# MCU_STM32_SCHE.net
KiCad netlist of a schematic drawn in Altium Designer
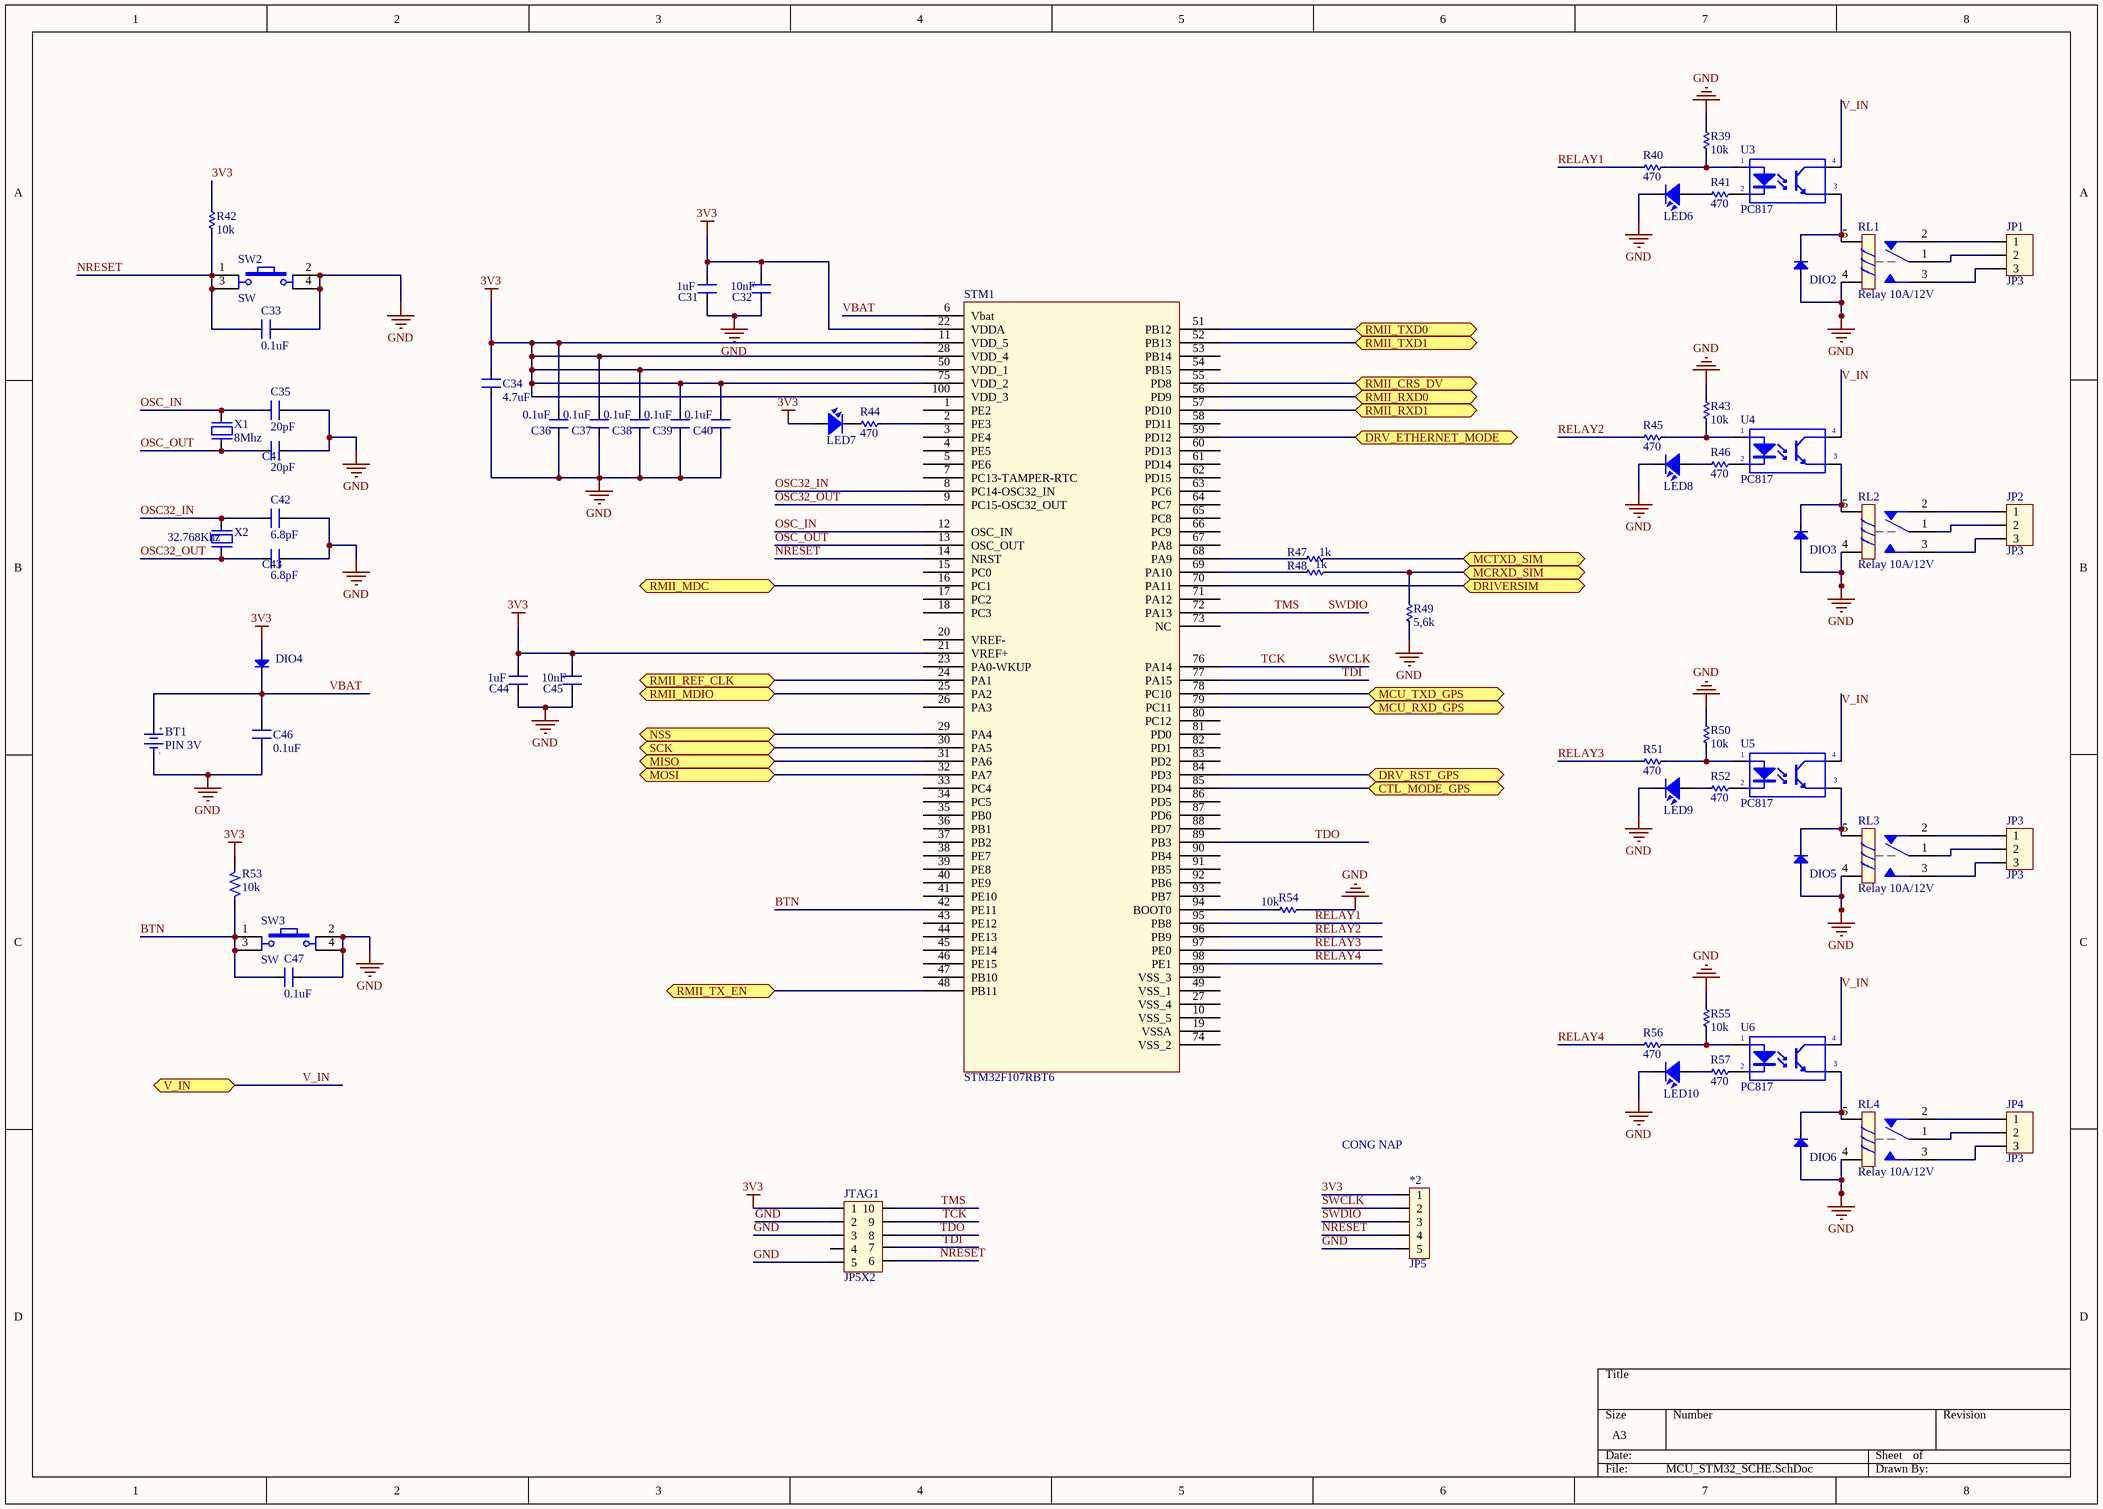
[diagram p0: MCU_STM32_SCHE.SchDoc]

(export (version "E")
  (design (tool "Eeschema 10.0.6"))
  (components
    (comp (ref "*2") (value "JP5") (footprint "JP5") (libsource (lib "syhaunguyen") (part "JP5")))
    (comp (ref "BT1")
      (value "PIN 3V")
      (footprint "PIN3V")
      (description "Battery 3VDC")
      (libsource (lib "syhaunguyen") (part "PIN 3V"))
    )
    (comp (ref "C31")
      (value "1uF")
      (footprint "res 0805 - duplicate")
      (description "Cap SMD")
      (libsource (lib "PART") (part "CM"))
    )
    (comp (ref "C32")
      (value "10nF")
      (footprint "res 0805 - duplicate")
      (description "Cap SMD")
      (libsource (lib "PART") (part "CM"))
    )
    (comp (ref "C33")
      (value "0.1uF")
      (footprint "res 0805 - duplicate")
      (description "Cap SMD")
      (libsource (lib "PART") (part "CM"))
    )
    (comp (ref "C34")
      (value "4.7uF")
      (footprint "res 0805 - duplicate")
      (fields (field (name "DESIGNED BY") "VanDungEvn"))
      (libsource (lib "syhaunguyen") (part "CN"))
    )
    (comp (ref "C35")
      (value "20pF")
      (footprint "res 0805 - duplicate")
      (description "Cap SMD")
      (libsource (lib "PART") (part "CM"))
    )
    (comp (ref "C36")
      (value "0.1uF")
      (footprint "res 0805 - duplicate")
      (description "Cap SMD")
      (libsource (lib "PART") (part "CM"))
    )
    (comp (ref "C37")
      (value "0.1uF")
      (footprint "res 0805 - duplicate")
      (description "Cap SMD")
      (libsource (lib "PART") (part "CM"))
    )
    (comp (ref "C38")
      (value "0.1uF")
      (footprint "res 0805 - duplicate")
      (description "Cap SMD")
      (libsource (lib "PART") (part "CM"))
    )
    (comp (ref "C39")
      (value "0.1uF")
      (footprint "res 0805 - duplicate")
      (description "Cap SMD")
      (libsource (lib "PART") (part "CM"))
    )
    (comp (ref "C40")
      (value "0.1uF")
      (footprint "res 0805 - duplicate")
      (description "Cap SMD")
      (libsource (lib "PART") (part "CM"))
    )
    (comp (ref "C41")
      (value "20pF")
      (footprint "res 0805 - duplicate")
      (description "Cap SMD")
      (libsource (lib "PART") (part "CM"))
    )
    (comp (ref "C42")
      (value "6.8pF")
      (footprint "res 0805 - duplicate")
      (description "Cap SMD")
      (libsource (lib "PART") (part "CM"))
    )
    (comp (ref "C43")
      (value "6.8pF")
      (footprint "res 0805 - duplicate")
      (description "Cap SMD")
      (libsource (lib "PART") (part "CM"))
    )
    (comp (ref "C44")
      (value "1uF")
      (footprint "res 0805 - duplicate")
      (description "Cap SMD")
      (libsource (lib "PART") (part "CM"))
    )
    (comp (ref "C45")
      (value "10nF")
      (footprint "res 0805 - duplicate")
      (description "Cap SMD")
      (libsource (lib "PART") (part "CM"))
    )
    (comp (ref "C46")
      (value "0.1uF")
      (footprint "res 0805 - duplicate")
      (description "Cap SMD")
      (libsource (lib "PART") (part "CM"))
    )
    (comp (ref "C47")
      (value "0.1uF")
      (footprint "res 0805 - duplicate")
      (description "Cap SMD")
      (libsource (lib "PART") (part "CM"))
    )
    (comp (ref "DIO2")
      (value "Diode SMD")
      (footprint "DIOT-SS24")
      (description "Default Diode")
      (fields (field (name "PUBLISHER") "Altium Limited"))
      (libsource (lib "LIBRARYabc") (part "Diode SMD"))
    )
    (comp (ref "DIO3")
      (value "Diode SMD")
      (footprint "DIOT-SS24")
      (description "Default Diode")
      (fields (field (name "PUBLISHER") "Altium Limited"))
      (libsource (lib "LIBRARYabc") (part "Diode SMD"))
    )
    (comp (ref "DIO4")
      (value "Diode SMD")
      (footprint "DIO-SMD-123")
      (description "Default Diode")
      (fields (field (name "PUBLISHER") "Altium Limited"))
      (libsource (lib "LIBRARYabc") (part "Diode SMD"))
    )
    (comp (ref "DIO5")
      (value "Diode SMD")
      (footprint "DIOT-SS24")
      (description "Default Diode")
      (fields (field (name "PUBLISHER") "Altium Limited"))
      (libsource (lib "LIBRARYabc") (part "Diode SMD"))
    )
    (comp (ref "DIO6")
      (value "Diode SMD")
      (footprint "DIOT-SS24")
      (description "Default Diode")
      (fields (field (name "PUBLISHER") "Altium Limited"))
      (libsource (lib "LIBRARYabc") (part "Diode SMD"))
    )
    (comp (ref "JP1")
      (value "JP3")
      (footprint "CON3")
      (description "Connector 3")
      (libsource (lib "syhaunguyen") (part "Con3"))
    )
    (comp (ref "JP2")
      (value "JP3")
      (footprint "CON3")
      (description "Connector 3")
      (libsource (lib "syhaunguyen") (part "Con3"))
    )
    (comp (ref "JP3")
      (value "JP3")
      (footprint "CON3")
      (description "Connector 3")
      (libsource (lib "syhaunguyen") (part "Con3"))
    )
    (comp (ref "JP4")
      (value "JP3")
      (footprint "CON3")
      (description "Connector 3")
      (libsource (lib "syhaunguyen") (part "Con3"))
    )
    (comp (ref "JTAG1") (value "JP5X2") (footprint "JP5X2") (libsource (lib "syhaunguyen") (part "JP5X2")))
    (comp (ref "LED6")
      (value "LED")
      (footprint "res 0805 - duplicate")
      (libsource (lib "LIBRARYabc") (part "LED SMD"))
    )
    (comp (ref "LED7")
      (value "LED")
      (footprint "res 0805 - duplicate")
      (libsource (lib "LIBRARYabc") (part "LED SMD"))
    )
    (comp (ref "LED8")
      (value "LED")
      (footprint "res 0805 - duplicate")
      (libsource (lib "LIBRARYabc") (part "LED SMD"))
    )
    (comp (ref "LED9")
      (value "LED")
      (footprint "res 0805 - duplicate")
      (libsource (lib "LIBRARYabc") (part "LED SMD"))
    )
    (comp (ref "LED10")
      (value "LED")
      (footprint "res 0805 - duplicate")
      (libsource (lib "LIBRARYabc") (part "LED SMD"))
    )
    (comp (ref "R39")
      (value "10k")
      (footprint "res 0805 - duplicate")
      (description "Resistor")
      (fields
        (field (name "MANUFACTURER") "Generic Components")
        (field (name "PUBLISHER") "Altium Hobart Technology Centre")
      )
      (libsource (lib "LIBRARYabc") (part "Res-SMD"))
    )
    (comp (ref "R40")
      (value "470")
      (footprint "res 0805 - duplicate")
      (description "Resistor")
      (fields
        (field (name "MANUFACTURER") "Generic Components")
        (field (name "PUBLISHER") "Altium Hobart Technology Centre")
      )
      (libsource (lib "LIBRARYabc") (part "Res-SMD"))
    )
    (comp (ref "R41")
      (value "470")
      (footprint "res 0805 - duplicate")
      (description "Resistor")
      (fields
        (field (name "MANUFACTURER") "Generic Components")
        (field (name "PUBLISHER") "Altium Hobart Technology Centre")
      )
      (libsource (lib "LIBRARYabc") (part "Res-SMD"))
    )
    (comp (ref "R42")
      (value "10k")
      (footprint "res 0805 - duplicate")
      (description "Resistor")
      (fields
        (field (name "MANUFACTURER") "Generic Components")
        (field (name "PUBLISHER") "Altium Hobart Technology Centre")
      )
      (libsource (lib "LIBRARYabc") (part "Res-SMD"))
    )
    (comp (ref "R43")
      (value "10k")
      (footprint "res 0805 - duplicate")
      (description "Resistor")
      (fields
        (field (name "MANUFACTURER") "Generic Components")
        (field (name "PUBLISHER") "Altium Hobart Technology Centre")
      )
      (libsource (lib "LIBRARYabc") (part "Res-SMD"))
    )
    (comp (ref "R44")
      (value "470")
      (footprint "res 0805 - duplicate")
      (description "Resistor")
      (fields
        (field (name "MANUFACTURER") "Generic Components")
        (field (name "PUBLISHER") "Altium Hobart Technology Centre")
      )
      (libsource (lib "LIBRARYabc") (part "Res-SMD"))
    )
    (comp (ref "R45")
      (value "470")
      (footprint "res 0805 - duplicate")
      (description "Resistor")
      (fields
        (field (name "MANUFACTURER") "Generic Components")
        (field (name "PUBLISHER") "Altium Hobart Technology Centre")
      )
      (libsource (lib "LIBRARYabc") (part "Res-SMD"))
    )
    (comp (ref "R46")
      (value "470")
      (footprint "res 0805 - duplicate")
      (description "Resistor")
      (fields
        (field (name "MANUFACTURER") "Generic Components")
        (field (name "PUBLISHER") "Altium Hobart Technology Centre")
      )
      (libsource (lib "LIBRARYabc") (part "Res-SMD"))
    )
    (comp (ref "R47")
      (value "1k")
      (footprint "res 0805 - duplicate")
      (description "Resistor")
      (fields
        (field (name "MANUFACTURER") "Generic Components")
        (field (name "PUBLISHER") "Altium Hobart Technology Centre")
      )
      (libsource (lib "LIBRARYabc") (part "Res-SMD"))
    )
    (comp (ref "R48")
      (value "1k")
      (footprint "res 0805 - duplicate")
      (description "Resistor")
      (fields
        (field (name "MANUFACTURER") "Generic Components")
        (field (name "PUBLISHER") "Altium Hobart Technology Centre")
      )
      (libsource (lib "LIBRARYabc") (part "Res-SMD"))
    )
    (comp (ref "R49")
      (value "5,6k")
      (footprint "res 0805 - duplicate")
      (description "Resistor")
      (fields
        (field (name "MANUFACTURER") "Generic Components")
        (field (name "PUBLISHER") "Altium Hobart Technology Centre")
      )
      (libsource (lib "LIBRARYabc") (part "Res-SMD"))
    )
    (comp (ref "R50")
      (value "10k")
      (footprint "res 0805 - duplicate")
      (description "Resistor")
      (fields
        (field (name "MANUFACTURER") "Generic Components")
        (field (name "PUBLISHER") "Altium Hobart Technology Centre")
      )
      (libsource (lib "LIBRARYabc") (part "Res-SMD"))
    )
    (comp (ref "R51")
      (value "470")
      (footprint "res 0805 - duplicate")
      (description "Resistor")
      (fields
        (field (name "MANUFACTURER") "Generic Components")
        (field (name "PUBLISHER") "Altium Hobart Technology Centre")
      )
      (libsource (lib "LIBRARYabc") (part "Res-SMD"))
    )
    (comp (ref "R52")
      (value "470")
      (footprint "res 0805 - duplicate")
      (description "Resistor")
      (fields
        (field (name "MANUFACTURER") "Generic Components")
        (field (name "PUBLISHER") "Altium Hobart Technology Centre")
      )
      (libsource (lib "LIBRARYabc") (part "Res-SMD"))
    )
    (comp (ref "R53")
      (value "10k")
      (footprint "res 0805 - duplicate")
      (description "Resistor 1/4W")
      (libsource (lib "syhaunguyen") (part "R"))
    )
    (comp (ref "R54")
      (value "10k")
      (footprint "res 0805 - duplicate")
      (description "Resistor")
      (fields
        (field (name "MANUFACTURER") "Generic Components")
        (field (name "PUBLISHER") "Altium Hobart Technology Centre")
      )
      (libsource (lib "LIBRARYabc") (part "Res-SMD"))
    )
    (comp (ref "R55")
      (value "10k")
      (footprint "res 0805 - duplicate")
      (description "Resistor")
      (fields
        (field (name "MANUFACTURER") "Generic Components")
        (field (name "PUBLISHER") "Altium Hobart Technology Centre")
      )
      (libsource (lib "LIBRARYabc") (part "Res-SMD"))
    )
    (comp (ref "R56")
      (value "470")
      (footprint "res 0805 - duplicate")
      (description "Resistor")
      (fields
        (field (name "MANUFACTURER") "Generic Components")
        (field (name "PUBLISHER") "Altium Hobart Technology Centre")
      )
      (libsource (lib "LIBRARYabc") (part "Res-SMD"))
    )
    (comp (ref "R57")
      (value "470")
      (footprint "res 0805 - duplicate")
      (description "Resistor")
      (fields
        (field (name "MANUFACTURER") "Generic Components")
        (field (name "PUBLISHER") "Altium Hobart Technology Centre")
      )
      (libsource (lib "LIBRARYabc") (part "Res-SMD"))
    )
    (comp (ref "RL1")
      (value "Relay 10A/12V")
      (footprint "RL_SPDT_10A")
      (description "Relay SPDT,10A - 12VDC 5 Pin")
      (libsource (lib "syhaunguyen") (part "Relay 1"))
    )
    (comp (ref "RL2")
      (value "Relay 10A/12V")
      (footprint "RL_SPDT_10A")
      (description "Relay SPDT,10A - 12VDC 5 Pin")
      (libsource (lib "syhaunguyen") (part "Relay 1"))
    )
    (comp (ref "RL3")
      (value "Relay 10A/12V")
      (footprint "RL_SPDT_10A")
      (description "Relay SPDT,10A - 12VDC 5 Pin")
      (libsource (lib "syhaunguyen") (part "Relay 1"))
    )
    (comp (ref "RL4")
      (value "Relay 10A/12V")
      (footprint "RL_SPDT_10A")
      (description "Relay SPDT,10A - 12VDC 5 Pin")
      (libsource (lib "syhaunguyen") (part "Relay 1"))
    )
    (comp (ref "STM1")
      (value "STM32F107RBT6")
      (footprint "STM32F107RBT6-LQFP100")
      (libsource (lib "my_lib") (part "STM32F107RBT6"))
    )
    (comp (ref "SW2")
      (value "SW")
      (footprint "button")
      (description "Switch button 4 pin")
      (libsource (lib "syhaunguyen") (part "SW4"))
    )
    (comp (ref "SW3")
      (value "SW")
      (footprint "button")
      (description "Switch button 4 pin")
      (libsource (lib "syhaunguyen") (part "SW4"))
    )
    (comp (ref "U3")
      (value "PC817")
      (footprint "DIP4/W0.3")
      (description "Single Opto")
      (libsource (lib "syhaunguyen") (part "PC817"))
    )
    (comp (ref "U4")
      (value "PC817")
      (footprint "DIP4/W0.3")
      (description "Single Opto")
      (libsource (lib "syhaunguyen") (part "PC817"))
    )
    (comp (ref "U5")
      (value "PC817")
      (footprint "DIP4/W0.3")
      (description "Single Opto")
      (libsource (lib "syhaunguyen") (part "PC817"))
    )
    (comp (ref "U6")
      (value "PC817")
      (footprint "DIP4/W0.3")
      (description "Single Opto")
      (libsource (lib "syhaunguyen") (part "PC817"))
    )
    (comp (ref "X1")
      (value "8Mhz")
      (footprint "XT2")
      (description "Crystal, 32.768 KHz, -40 to 85 degC, 3.2 x 1.5 x 0.9 mm SMD")
      (libsource (lib "LIBRARYabc") (part "XT2"))
    )
    (comp (ref "X2")
      (value "32.768Khz")
      (footprint "XT2")
      (description "Crystal, 32.768 KHz, -40 to 85 degC, 3.2 x 1.5 x 0.9 mm SMD")
      (libsource (lib "LIBRARYabc") (part "XT2"))
    )
  )
  (nets
    (net (code "1") (name "/BTN") (class "Default")
      (node (ref "C47") (pin "1") (pinfunction "1_1") (pintype "passive"))
      (node (ref "R53") (pin "1") (pinfunction "1_1") (pintype "passive"))
      (node (ref "STM1") (pin "42") (pinfunction "PE11_42") (pintype "passive"))
      (node (ref "SW3") (pin "1") (pintype "passive"))
      (node (ref "SW3") (pin "3") (pintype "passive"))
    )
    (net (code "2") (name "/CTL_MODE_GPS") (class "Default")
      (node (ref "STM1") (pin "85") (pinfunction "PD4_85") (pintype "passive"))
    )
    (net (code "3") (name "/DRIVERSIM") (class "Default")
      (node (ref "STM1") (pin "70") (pinfunction "PA11_70") (pintype "passive"))
    )
    (net (code "4") (name "/DRV_ETHERNET_MODE") (class "Default")
      (node (ref "STM1") (pin "59") (pinfunction "PD12_59") (pintype "passive"))
    )
    (net (code "5") (name "/DRV_RST_GPS") (class "Default")
      (node (ref "STM1") (pin "84") (pinfunction "PD3_84") (pintype "passive"))
    )
    (net (code "6") (name "/MCRXD_SIM") (class "Default")
      (node (ref "R48") (pin "1") (pinfunction "1_1") (pintype "passive"))
      (node (ref "R49") (pin "1") (pinfunction "1_1") (pintype "passive"))
    )
    (net (code "7") (name "/MCTXD_SIM") (class "Default")
      (node (ref "R47") (pin "1") (pinfunction "1_1") (pintype "passive"))
    )
    (net (code "8") (name "/MCU_RXD_GPS") (class "Default")
      (node (ref "STM1") (pin "79") (pinfunction "PC11_79") (pintype "passive"))
    )
    (net (code "9") (name "/MCU_TXD_GPS") (class "Default")
      (node (ref "STM1") (pin "78") (pinfunction "PC10_78") (pintype "passive"))
    )
    (net (code "10") (name "/MISO") (class "Default")
      (node (ref "STM1") (pin "31") (pinfunction "PA6_31") (pintype "passive"))
    )
    (net (code "11") (name "/MOSI") (class "Default")
      (node (ref "STM1") (pin "32") (pinfunction "PA7_32") (pintype "passive"))
    )
    (net (code "12") (name "/NRESET") (class "Default")
      (node (ref "*2") (pin "4") (pinfunction "4_4") (pintype "passive"))
      (node (ref "C33") (pin "1") (pinfunction "1_1") (pintype "passive"))
      (node (ref "JTAG1") (pin "6") (pinfunction "6_6") (pintype "passive"))
      (node (ref "R42") (pin "2") (pinfunction "2_2") (pintype "passive"))
      (node (ref "STM1") (pin "14") (pinfunction "NRST_14") (pintype "passive"))
      (node (ref "SW2") (pin "1") (pintype "passive"))
      (node (ref "SW2") (pin "3") (pintype "passive"))
    )
    (net (code "13") (name "/NSS") (class "Default")
      (node (ref "STM1") (pin "29") (pinfunction "PA4_29") (pintype "passive"))
    )
    (net (code "14") (name "/OSC32_IN") (class "Default")
      (node (ref "C42") (pin "1") (pinfunction "1_1") (pintype "passive"))
      (node (ref "STM1") (pin "8") (pinfunction "PC14-OSC32_IN_8") (pintype "passive"))
      (node (ref "X2") (pin "2") (pinfunction "2_2") (pintype "passive"))
    )
    (net (code "15") (name "/OSC32_OUT") (class "Default")
      (node (ref "C43") (pin "1") (pinfunction "1_1") (pintype "passive"))
      (node (ref "STM1") (pin "9") (pinfunction "PC15-OSC32_OUT_9") (pintype "passive"))
      (node (ref "X2") (pin "1") (pinfunction "1_1") (pintype "passive"))
    )
    (net (code "16") (name "/OSC_IN") (class "Default")
      (node (ref "C35") (pin "1") (pinfunction "1_1") (pintype "passive"))
      (node (ref "STM1") (pin "12") (pinfunction "OSC_IN_12") (pintype "passive"))
      (node (ref "X1") (pin "2") (pinfunction "2_2") (pintype "passive"))
    )
    (net (code "17") (name "/OSC_OUT") (class "Default")
      (node (ref "C41") (pin "1") (pinfunction "1_1") (pintype "passive"))
      (node (ref "STM1") (pin "13") (pinfunction "OSC_OUT_13") (pintype "passive"))
      (node (ref "X1") (pin "1") (pinfunction "1_1") (pintype "passive"))
    )
    (net (code "18") (name "/RELAY1") (class "Default")
      (node (ref "R40") (pin "2") (pinfunction "2_2") (pintype "passive"))
      (node (ref "STM1") (pin "95") (pinfunction "PB8_95") (pintype "passive"))
    )
    (net (code "19") (name "/RELAY2") (class "Default")
      (node (ref "R45") (pin "2") (pinfunction "2_2") (pintype "passive"))
      (node (ref "STM1") (pin "96") (pinfunction "PB9_96") (pintype "passive"))
    )
    (net (code "20") (name "/RELAY3") (class "Default")
      (node (ref "R51") (pin "2") (pinfunction "2_2") (pintype "passive"))
      (node (ref "STM1") (pin "97") (pinfunction "PE0_97") (pintype "passive"))
    )
    (net (code "21") (name "/RELAY4") (class "Default")
      (node (ref "R56") (pin "2") (pinfunction "2_2") (pintype "passive"))
      (node (ref "STM1") (pin "98") (pinfunction "PE1_98") (pintype "passive"))
    )
    (net (code "22") (name "/RMII_CRS_DV") (class "Default")
      (node (ref "STM1") (pin "55") (pinfunction "PD8_55") (pintype "passive"))
    )
    (net (code "23") (name "/RMII_MDC") (class "Default")
      (node (ref "STM1") (pin "16") (pinfunction "PC1_16") (pintype "passive"))
    )
    (net (code "24") (name "/RMII_MDIO") (class "Default")
      (node (ref "STM1") (pin "25") (pinfunction "PA2_25") (pintype "passive"))
    )
    (net (code "25") (name "/RMII_REF_CLK") (class "Default")
      (node (ref "STM1") (pin "24") (pinfunction "PA1_24") (pintype "passive"))
    )
    (net (code "26") (name "/RMII_RXD0") (class "Default")
      (node (ref "STM1") (pin "56") (pinfunction "PD9_56") (pintype "passive"))
    )
    (net (code "27") (name "/RMII_RXD1") (class "Default")
      (node (ref "STM1") (pin "57") (pinfunction "PD10_57") (pintype "passive"))
    )
    (net (code "28") (name "/RMII_TXD0") (class "Default")
      (node (ref "STM1") (pin "51") (pinfunction "PB12_51") (pintype "passive"))
    )
    (net (code "29") (name "/RMII_TXD1") (class "Default")
      (node (ref "STM1") (pin "52") (pinfunction "PB13_52") (pintype "passive"))
    )
    (net (code "30") (name "/RMII_TX_EN") (class "Default")
      (node (ref "STM1") (pin "48") (pinfunction "PB11_48") (pintype "passive"))
    )
    (net (code "31") (name "/SCK") (class "Default")
      (node (ref "STM1") (pin "30") (pinfunction "PA5_30") (pintype "passive"))
    )
    (net (code "32") (name "/SWCLK") (class "Default")
      (node (ref "*2") (pin "2") (pinfunction "2_2") (pintype "passive"))
      (node (ref "JTAG1") (pin "9") (pinfunction "9_9") (pintype "passive"))
      (node (ref "STM1") (pin "76") (pinfunction "PA14_76") (pintype "passive"))
    )
    (net (code "33") (name "/SWDIO") (class "Default")
      (node (ref "*2") (pin "3") (pinfunction "3_3") (pintype "passive"))
      (node (ref "JTAG1") (pin "10") (pinfunction "10_10") (pintype "passive"))
      (node (ref "STM1") (pin "72") (pinfunction "PA13_72") (pintype "passive"))
    )
    (net (code "34") (name "/TDI") (class "Default")
      (node (ref "JTAG1") (pin "7") (pinfunction "7_7") (pintype "passive"))
      (node (ref "STM1") (pin "77") (pinfunction "PA15_77") (pintype "passive"))
    )
    (net (code "35") (name "/TDO") (class "Default")
      (node (ref "JTAG1") (pin "8") (pinfunction "8_8") (pintype "passive"))
      (node (ref "STM1") (pin "89") (pinfunction "PB3_89") (pintype "passive"))
    )
    (net (code "36") (name "/VBAT") (class "Default")
      (node (ref "BT1") (pin "1") (pinfunction "+3V_1") (pintype "passive"))
      (node (ref "C46") (pin "2") (pinfunction "2_2") (pintype "passive"))
      (node (ref "DIO4") (pin "2") (pinfunction "K_2") (pintype "passive"))
      (node (ref "STM1") (pin "6") (pinfunction "Vbat_6") (pintype "passive"))
    )
    (net (code "37") (name "/V_IN") (class "Default")
      (node (ref "U3") (pin "4") (pinfunction "C_4") (pintype "passive"))
      (node (ref "U4") (pin "4") (pinfunction "C_4") (pintype "passive"))
      (node (ref "U5") (pin "4") (pinfunction "C_4") (pintype "passive"))
      (node (ref "U6") (pin "4") (pinfunction "C_4") (pintype "passive"))
    )
    (net (code "38") (name "3V3") (class "Default")
      (node (ref "*2") (pin "1") (pinfunction "1_1") (pintype "passive"))
      (node (ref "C31") (pin "2") (pinfunction "2_2") (pintype "passive"))
      (node (ref "C32") (pin "2") (pinfunction "2_2") (pintype "passive"))
      (node (ref "C34") (pin "2") (pinfunction "2_2") (pintype "passive"))
      (node (ref "C36") (pin "2") (pinfunction "2_2") (pintype "passive"))
      (node (ref "C37") (pin "2") (pinfunction "2_2") (pintype "passive"))
      (node (ref "C38") (pin "2") (pinfunction "2_2") (pintype "passive"))
      (node (ref "C39") (pin "2") (pinfunction "2_2") (pintype "passive"))
      (node (ref "C40") (pin "2") (pinfunction "2_2") (pintype "passive"))
      (node (ref "C44") (pin "2") (pinfunction "2_2") (pintype "passive"))
      (node (ref "C45") (pin "2") (pinfunction "2_2") (pintype "passive"))
      (node (ref "DIO4") (pin "1") (pinfunction "A_1") (pintype "passive"))
      (node (ref "JTAG1") (pin "1") (pinfunction "1_1") (pintype "passive"))
      (node (ref "LED7") (pin "1") (pinfunction "1_1") (pintype "passive"))
      (node (ref "R42") (pin "1") (pinfunction "1_1") (pintype "passive"))
      (node (ref "R53") (pin "2") (pinfunction "2_2") (pintype "passive"))
      (node (ref "STM1") (pin "100") (pinfunction "VDD_3_100") (pintype "passive"))
      (node (ref "STM1") (pin "11") (pinfunction "VDD_5_11") (pintype "passive"))
      (node (ref "STM1") (pin "21") (pinfunction "VREF+_21") (pintype "passive"))
      (node (ref "STM1") (pin "22") (pinfunction "VDDA_22") (pintype "passive"))
      (node (ref "STM1") (pin "28") (pinfunction "VDD_4_28") (pintype "passive"))
      (node (ref "STM1") (pin "50") (pinfunction "VDD_1_50") (pintype "passive"))
      (node (ref "STM1") (pin "75") (pinfunction "VDD_2_75") (pintype "passive"))
    )
    (net (code "39") (name "GND") (class "Default")
      (node (ref "*2") (pin "5") (pinfunction "5_5") (pintype "passive"))
      (node (ref "BT1") (pin "2") (pinfunction "GND_2") (pintype "passive"))
      (node (ref "C31") (pin "1") (pinfunction "1_1") (pintype "passive"))
      (node (ref "C32") (pin "1") (pinfunction "1_1") (pintype "passive"))
      (node (ref "C33") (pin "2") (pinfunction "2_2") (pintype "passive"))
      (node (ref "C34") (pin "1") (pinfunction "1_1") (pintype "passive"))
      (node (ref "C35") (pin "2") (pinfunction "2_2") (pintype "passive"))
      (node (ref "C36") (pin "1") (pinfunction "1_1") (pintype "passive"))
      (node (ref "C37") (pin "1") (pinfunction "1_1") (pintype "passive"))
      (node (ref "C38") (pin "1") (pinfunction "1_1") (pintype "passive"))
      (node (ref "C39") (pin "1") (pinfunction "1_1") (pintype "passive"))
      (node (ref "C40") (pin "1") (pinfunction "1_1") (pintype "passive"))
      (node (ref "C41") (pin "2") (pinfunction "2_2") (pintype "passive"))
      (node (ref "C42") (pin "2") (pinfunction "2_2") (pintype "passive"))
      (node (ref "C43") (pin "2") (pinfunction "2_2") (pintype "passive"))
      (node (ref "C44") (pin "1") (pinfunction "1_1") (pintype "passive"))
      (node (ref "C45") (pin "1") (pinfunction "1_1") (pintype "passive"))
      (node (ref "C46") (pin "1") (pinfunction "1_1") (pintype "passive"))
      (node (ref "C47") (pin "2") (pinfunction "2_2") (pintype "passive"))
      (node (ref "DIO2") (pin "1") (pinfunction "A_1") (pintype "passive"))
      (node (ref "DIO3") (pin "1") (pinfunction "A_1") (pintype "passive"))
      (node (ref "DIO5") (pin "1") (pinfunction "A_1") (pintype "passive"))
      (node (ref "DIO6") (pin "1") (pinfunction "A_1") (pintype "passive"))
      (node (ref "JTAG1") (pin "2") (pinfunction "2_2") (pintype "passive"))
      (node (ref "JTAG1") (pin "3") (pinfunction "3_3") (pintype "passive"))
      (node (ref "JTAG1") (pin "5") (pinfunction "5_5") (pintype "passive"))
      (node (ref "LED10") (pin "2") (pinfunction "2_2") (pintype "passive"))
      (node (ref "LED6") (pin "2") (pinfunction "2_2") (pintype "passive"))
      (node (ref "LED8") (pin "2") (pinfunction "2_2") (pintype "passive"))
      (node (ref "LED9") (pin "2") (pinfunction "2_2") (pintype "passive"))
      (node (ref "R39") (pin "1") (pinfunction "1_1") (pintype "passive"))
      (node (ref "R43") (pin "1") (pinfunction "1_1") (pintype "passive"))
      (node (ref "R49") (pin "2") (pinfunction "2_2") (pintype "passive"))
      (node (ref "R50") (pin "1") (pinfunction "1_1") (pintype "passive"))
      (node (ref "R54") (pin "2") (pinfunction "2_2") (pintype "passive"))
      (node (ref "R55") (pin "1") (pinfunction "1_1") (pintype "passive"))
      (node (ref "RL1") (pin "4") (pinfunction "4_4") (pintype "passive"))
      (node (ref "RL2") (pin "4") (pinfunction "4_4") (pintype "passive"))
      (node (ref "RL3") (pin "4") (pinfunction "4_4") (pintype "passive"))
      (node (ref "RL4") (pin "4") (pinfunction "4_4") (pintype "passive"))
      (node (ref "SW2") (pin "2") (pintype "passive"))
      (node (ref "SW2") (pin "4") (pintype "passive"))
      (node (ref "SW3") (pin "2") (pintype "passive"))
      (node (ref "SW3") (pin "4") (pintype "passive"))
    )
    (net (code "40") (name "Net-(DIO2-K)") (class "Default")
      (node (ref "DIO2") (pin "2") (pinfunction "K_2") (pintype "passive"))
      (node (ref "RL1") (pin "5") (pinfunction "5_5") (pintype "passive"))
      (node (ref "U3") (pin "3") (pinfunction "E_3") (pintype "passive"))
    )
    (net (code "41") (name "Net-(DIO3-K)") (class "Default")
      (node (ref "DIO3") (pin "2") (pinfunction "K_2") (pintype "passive"))
      (node (ref "RL2") (pin "5") (pinfunction "5_5") (pintype "passive"))
      (node (ref "U4") (pin "3") (pinfunction "E_3") (pintype "passive"))
    )
    (net (code "42") (name "Net-(DIO5-K)") (class "Default")
      (node (ref "DIO5") (pin "2") (pinfunction "K_2") (pintype "passive"))
      (node (ref "RL3") (pin "5") (pinfunction "5_5") (pintype "passive"))
      (node (ref "U5") (pin "3") (pinfunction "E_3") (pintype "passive"))
    )
    (net (code "43") (name "Net-(DIO6-K)") (class "Default")
      (node (ref "DIO6") (pin "2") (pinfunction "K_2") (pintype "passive"))
      (node (ref "RL4") (pin "5") (pinfunction "5_5") (pintype "passive"))
      (node (ref "U6") (pin "3") (pinfunction "E_3") (pintype "passive"))
    )
    (net (code "44") (name "Net-(JP1-Pad1)") (class "Default")
      (node (ref "JP1") (pin "1") (pinfunction "1_1") (pintype "passive"))
      (node (ref "RL1") (pin "2") (pinfunction "2_2") (pintype "passive"))
    )
    (net (code "45") (name "Net-(JP1-Pad2)") (class "Default")
      (node (ref "JP1") (pin "2") (pinfunction "2_2") (pintype "passive"))
      (node (ref "RL1") (pin "1") (pinfunction "1_1") (pintype "passive"))
    )
    (net (code "46") (name "Net-(JP1-Pad3)") (class "Default")
      (node (ref "JP1") (pin "3") (pinfunction "3_3") (pintype "passive"))
      (node (ref "RL1") (pin "3") (pinfunction "3_3") (pintype "passive"))
    )
    (net (code "47") (name "Net-(JP2-Pad1)") (class "Default")
      (node (ref "JP2") (pin "1") (pinfunction "1_1") (pintype "passive"))
      (node (ref "RL2") (pin "2") (pinfunction "2_2") (pintype "passive"))
    )
    (net (code "48") (name "Net-(JP2-Pad2)") (class "Default")
      (node (ref "JP2") (pin "2") (pinfunction "2_2") (pintype "passive"))
      (node (ref "RL2") (pin "1") (pinfunction "1_1") (pintype "passive"))
    )
    (net (code "49") (name "Net-(JP2-Pad3)") (class "Default")
      (node (ref "JP2") (pin "3") (pinfunction "3_3") (pintype "passive"))
      (node (ref "RL2") (pin "3") (pinfunction "3_3") (pintype "passive"))
    )
    (net (code "50") (name "Net-(JP3-Pad1)") (class "Default")
      (node (ref "JP3") (pin "1") (pinfunction "1_1") (pintype "passive"))
      (node (ref "RL3") (pin "2") (pinfunction "2_2") (pintype "passive"))
    )
    (net (code "51") (name "Net-(JP3-Pad2)") (class "Default")
      (node (ref "JP3") (pin "2") (pinfunction "2_2") (pintype "passive"))
      (node (ref "RL3") (pin "1") (pinfunction "1_1") (pintype "passive"))
    )
    (net (code "52") (name "Net-(JP3-Pad3)") (class "Default")
      (node (ref "JP3") (pin "3") (pinfunction "3_3") (pintype "passive"))
      (node (ref "RL3") (pin "3") (pinfunction "3_3") (pintype "passive"))
    )
    (net (code "53") (name "Net-(JP4-Pad1)") (class "Default")
      (node (ref "JP4") (pin "1") (pinfunction "1_1") (pintype "passive"))
      (node (ref "RL4") (pin "2") (pinfunction "2_2") (pintype "passive"))
    )
    (net (code "54") (name "Net-(JP4-Pad2)") (class "Default")
      (node (ref "JP4") (pin "2") (pinfunction "2_2") (pintype "passive"))
      (node (ref "RL4") (pin "1") (pinfunction "1_1") (pintype "passive"))
    )
    (net (code "55") (name "Net-(JP4-Pad3)") (class "Default")
      (node (ref "JP4") (pin "3") (pinfunction "3_3") (pintype "passive"))
      (node (ref "RL4") (pin "3") (pinfunction "3_3") (pintype "passive"))
    )
    (net (code "56") (name "Net-(LED6-Pad1)") (class "Default")
      (node (ref "LED6") (pin "1") (pinfunction "1_1") (pintype "passive"))
      (node (ref "R41") (pin "2") (pinfunction "2_2") (pintype "passive"))
    )
    (net (code "57") (name "Net-(LED7-Pad2)") (class "Default")
      (node (ref "LED7") (pin "2") (pinfunction "2_2") (pintype "passive"))
      (node (ref "R44") (pin "2") (pinfunction "2_2") (pintype "passive"))
    )
    (net (code "58") (name "Net-(LED8-Pad1)") (class "Default")
      (node (ref "LED8") (pin "1") (pinfunction "1_1") (pintype "passive"))
      (node (ref "R46") (pin "2") (pinfunction "2_2") (pintype "passive"))
    )
    (net (code "59") (name "Net-(LED9-Pad1)") (class "Default")
      (node (ref "LED9") (pin "1") (pinfunction "1_1") (pintype "passive"))
      (node (ref "R52") (pin "2") (pinfunction "2_2") (pintype "passive"))
    )
    (net (code "60") (name "Net-(LED10-Pad1)") (class "Default")
      (node (ref "LED10") (pin "1") (pinfunction "1_1") (pintype "passive"))
      (node (ref "R57") (pin "2") (pinfunction "2_2") (pintype "passive"))
    )
    (net (code "61") (name "Net-(STM1-BOOT0)") (class "Default")
      (node (ref "R54") (pin "1") (pinfunction "1_1") (pintype "passive"))
      (node (ref "STM1") (pin "94") (pinfunction "BOOT0_94") (pintype "passive"))
    )
    (net (code "62") (name "Net-(STM1-PA9)") (class "Default")
      (node (ref "R47") (pin "2") (pinfunction "2_2") (pintype "passive"))
      (node (ref "STM1") (pin "68") (pinfunction "PA9_68") (pintype "passive"))
    )
    (net (code "63") (name "Net-(STM1-PA10)") (class "Default")
      (node (ref "R48") (pin "2") (pinfunction "2_2") (pintype "passive"))
      (node (ref "STM1") (pin "69") (pinfunction "PA10_69") (pintype "passive"))
    )
    (net (code "64") (name "Net-(STM1-PE3)") (class "Default")
      (node (ref "R44") (pin "1") (pinfunction "1_1") (pintype "passive"))
      (node (ref "STM1") (pin "2") (pinfunction "PE3_2") (pintype "passive"))
    )
    (net (code "65") (name "Net-(U3-A)") (class "Default")
      (node (ref "R39") (pin "2") (pinfunction "2_2") (pintype "passive"))
      (node (ref "R40") (pin "1") (pinfunction "1_1") (pintype "passive"))
      (node (ref "U3") (pin "1") (pinfunction "A_1") (pintype "passive"))
    )
    (net (code "66") (name "Net-(U3-K)") (class "Default")
      (node (ref "R41") (pin "1") (pinfunction "1_1") (pintype "passive"))
      (node (ref "U3") (pin "2") (pinfunction "K_2") (pintype "passive"))
    )
    (net (code "67") (name "Net-(U4-A)") (class "Default")
      (node (ref "R43") (pin "2") (pinfunction "2_2") (pintype "passive"))
      (node (ref "R45") (pin "1") (pinfunction "1_1") (pintype "passive"))
      (node (ref "U4") (pin "1") (pinfunction "A_1") (pintype "passive"))
    )
    (net (code "68") (name "Net-(U4-K)") (class "Default")
      (node (ref "R46") (pin "1") (pinfunction "1_1") (pintype "passive"))
      (node (ref "U4") (pin "2") (pinfunction "K_2") (pintype "passive"))
    )
    (net (code "69") (name "Net-(U5-A)") (class "Default")
      (node (ref "R50") (pin "2") (pinfunction "2_2") (pintype "passive"))
      (node (ref "R51") (pin "1") (pinfunction "1_1") (pintype "passive"))
      (node (ref "U5") (pin "1") (pinfunction "A_1") (pintype "passive"))
    )
    (net (code "70") (name "Net-(U5-K)") (class "Default")
      (node (ref "R52") (pin "1") (pinfunction "1_1") (pintype "passive"))
      (node (ref "U5") (pin "2") (pinfunction "K_2") (pintype "passive"))
    )
    (net (code "71") (name "Net-(U6-A)") (class "Default")
      (node (ref "R55") (pin "2") (pinfunction "2_2") (pintype "passive"))
      (node (ref "R56") (pin "1") (pinfunction "1_1") (pintype "passive"))
      (node (ref "U6") (pin "1") (pinfunction "A_1") (pintype "passive"))
    )
    (net (code "72") (name "Net-(U6-K)") (class "Default")
      (node (ref "R57") (pin "1") (pinfunction "1_1") (pintype "passive"))
      (node (ref "U6") (pin "2") (pinfunction "K_2") (pintype "passive"))
    )
    (net (code "73") (name "unconnected-(JTAG1-Pad4)") (class "Default")
      (node (ref "JTAG1") (pin "4") (pinfunction "4_4") (pintype "passive"))
    )
    (net (code "74") (name "unconnected-(STM1-NC-Pad73)") (class "Default")
      (node (ref "STM1") (pin "73") (pinfunction "NC_73") (pintype "passive"))
    )
    (net (code "75") (name "unconnected-(STM1-PA0-WKUP-Pad23)") (class "Default")
      (node (ref "STM1") (pin "23") (pinfunction "PA0-WKUP_23") (pintype "passive"))
    )
    (net (code "76") (name "unconnected-(STM1-PA3-Pad26)") (class "Default")
      (node (ref "STM1") (pin "26") (pinfunction "PA3_26") (pintype "passive"))
    )
    (net (code "77") (name "unconnected-(STM1-PA8-Pad67)") (class "Default")
      (node (ref "STM1") (pin "67") (pinfunction "PA8_67") (pintype "passive"))
    )
    (net (code "78") (name "unconnected-(STM1-PA12-Pad71)") (class "Default")
      (node (ref "STM1") (pin "71") (pinfunction "PA12_71") (pintype "passive"))
    )
    (net (code "79") (name "unconnected-(STM1-PB0-Pad35)") (class "Default")
      (node (ref "STM1") (pin "35") (pinfunction "PB0_35") (pintype "passive"))
    )
    (net (code "80") (name "unconnected-(STM1-PB1-Pad36)") (class "Default")
      (node (ref "STM1") (pin "36") (pinfunction "PB1_36") (pintype "passive"))
    )
    (net (code "81") (name "unconnected-(STM1-PB2-Pad37)") (class "Default")
      (node (ref "STM1") (pin "37") (pinfunction "PB2_37") (pintype "passive"))
    )
    (net (code "82") (name "unconnected-(STM1-PB4-Pad90)") (class "Default")
      (node (ref "STM1") (pin "90") (pinfunction "PB4_90") (pintype "passive"))
    )
    (net (code "83") (name "unconnected-(STM1-PB5-Pad91)") (class "Default")
      (node (ref "STM1") (pin "91") (pinfunction "PB5_91") (pintype "passive"))
    )
    (net (code "84") (name "unconnected-(STM1-PB6-Pad92)") (class "Default")
      (node (ref "STM1") (pin "92") (pinfunction "PB6_92") (pintype "passive"))
    )
    (net (code "85") (name "unconnected-(STM1-PB7-Pad93)") (class "Default")
      (node (ref "STM1") (pin "93") (pinfunction "PB7_93") (pintype "passive"))
    )
    (net (code "86") (name "unconnected-(STM1-PB10-Pad47)") (class "Default")
      (node (ref "STM1") (pin "47") (pinfunction "PB10_47") (pintype "passive"))
    )
    (net (code "87") (name "unconnected-(STM1-PB14-Pad53)") (class "Default")
      (node (ref "STM1") (pin "53") (pinfunction "PB14_53") (pintype "passive"))
    )
    (net (code "88") (name "unconnected-(STM1-PB15-Pad54)") (class "Default")
      (node (ref "STM1") (pin "54") (pinfunction "PB15_54") (pintype "passive"))
    )
    (net (code "89") (name "unconnected-(STM1-PC0-Pad15)") (class "Default")
      (node (ref "STM1") (pin "15") (pinfunction "PC0_15") (pintype "passive"))
    )
    (net (code "90") (name "unconnected-(STM1-PC2-Pad17)") (class "Default")
      (node (ref "STM1") (pin "17") (pinfunction "PC2_17") (pintype "passive"))
    )
    (net (code "91") (name "unconnected-(STM1-PC3-Pad18)") (class "Default")
      (node (ref "STM1") (pin "18") (pinfunction "PC3_18") (pintype "passive"))
    )
    (net (code "92") (name "unconnected-(STM1-PC4-Pad33)") (class "Default")
      (node (ref "STM1") (pin "33") (pinfunction "PC4_33") (pintype "passive"))
    )
    (net (code "93") (name "unconnected-(STM1-PC5-Pad34)") (class "Default")
      (node (ref "STM1") (pin "34") (pinfunction "PC5_34") (pintype "passive"))
    )
    (net (code "94") (name "unconnected-(STM1-PC6-Pad63)") (class "Default")
      (node (ref "STM1") (pin "63") (pinfunction "PC6_63") (pintype "passive"))
    )
    (net (code "95") (name "unconnected-(STM1-PC7-Pad64)") (class "Default")
      (node (ref "STM1") (pin "64") (pinfunction "PC7_64") (pintype "passive"))
    )
    (net (code "96") (name "unconnected-(STM1-PC8-Pad65)") (class "Default")
      (node (ref "STM1") (pin "65") (pinfunction "PC8_65") (pintype "passive"))
    )
    (net (code "97") (name "unconnected-(STM1-PC9-Pad66)") (class "Default")
      (node (ref "STM1") (pin "66") (pinfunction "PC9_66") (pintype "passive"))
    )
    (net (code "98") (name "unconnected-(STM1-PC12-Pad80)") (class "Default")
      (node (ref "STM1") (pin "80") (pinfunction "PC12_80") (pintype "passive"))
    )
    (net (code "99") (name "unconnected-(STM1-PC13-TAMPER-RTC-Pad7)") (class "Default")
      (node (ref "STM1") (pin "7") (pinfunction "PC13-TAMPER-RTC_7") (pintype "passive"))
    )
    (net (code "100") (name "unconnected-(STM1-PD0-Pad81)") (class "Default")
      (node (ref "STM1") (pin "81") (pinfunction "PD0_81") (pintype "passive"))
    )
    (net (code "101") (name "unconnected-(STM1-PD1-Pad82)") (class "Default")
      (node (ref "STM1") (pin "82") (pinfunction "PD1_82") (pintype "passive"))
    )
    (net (code "102") (name "unconnected-(STM1-PD2-Pad83)") (class "Default")
      (node (ref "STM1") (pin "83") (pinfunction "PD2_83") (pintype "passive"))
    )
    (net (code "103") (name "unconnected-(STM1-PD5-Pad86)") (class "Default")
      (node (ref "STM1") (pin "86") (pinfunction "PD5_86") (pintype "passive"))
    )
    (net (code "104") (name "unconnected-(STM1-PD6-Pad87)") (class "Default")
      (node (ref "STM1") (pin "87") (pinfunction "PD6_87") (pintype "passive"))
    )
    (net (code "105") (name "unconnected-(STM1-PD7-Pad88)") (class "Default")
      (node (ref "STM1") (pin "88") (pinfunction "PD7_88") (pintype "passive"))
    )
    (net (code "106") (name "unconnected-(STM1-PD11-Pad58)") (class "Default")
      (node (ref "STM1") (pin "58") (pinfunction "PD11_58") (pintype "passive"))
    )
    (net (code "107") (name "unconnected-(STM1-PD13-Pad60)") (class "Default")
      (node (ref "STM1") (pin "60") (pinfunction "PD13_60") (pintype "passive"))
    )
    (net (code "108") (name "unconnected-(STM1-PD14-Pad61)") (class "Default")
      (node (ref "STM1") (pin "61") (pinfunction "PD14_61") (pintype "passive"))
    )
    (net (code "109") (name "unconnected-(STM1-PD15-Pad62)") (class "Default")
      (node (ref "STM1") (pin "62") (pinfunction "PD15_62") (pintype "passive"))
    )
    (net (code "110") (name "unconnected-(STM1-PE2-Pad1)") (class "Default")
      (node (ref "STM1") (pin "1") (pinfunction "PE2_1") (pintype "passive"))
    )
    (net (code "111") (name "unconnected-(STM1-PE4-Pad3)") (class "Default")
      (node (ref "STM1") (pin "3") (pinfunction "PE4_3") (pintype "passive"))
    )
    (net (code "112") (name "unconnected-(STM1-PE5-Pad4)") (class "Default")
      (node (ref "STM1") (pin "4") (pinfunction "PE5_4") (pintype "passive"))
    )
    (net (code "113") (name "unconnected-(STM1-PE6-Pad5)") (class "Default")
      (node (ref "STM1") (pin "5") (pinfunction "PE6_5") (pintype "passive"))
    )
    (net (code "114") (name "unconnected-(STM1-PE7-Pad38)") (class "Default")
      (node (ref "STM1") (pin "38") (pinfunction "PE7_38") (pintype "passive"))
    )
    (net (code "115") (name "unconnected-(STM1-PE8-Pad39)") (class "Default")
      (node (ref "STM1") (pin "39") (pinfunction "PE8_39") (pintype "passive"))
    )
    (net (code "116") (name "unconnected-(STM1-PE9-Pad40)") (class "Default")
      (node (ref "STM1") (pin "40") (pinfunction "PE9_40") (pintype "passive"))
    )
    (net (code "117") (name "unconnected-(STM1-PE10-Pad41)") (class "Default")
      (node (ref "STM1") (pin "41") (pinfunction "PE10_41") (pintype "passive"))
    )
    (net (code "118") (name "unconnected-(STM1-PE12-Pad43)") (class "Default")
      (node (ref "STM1") (pin "43") (pinfunction "PE12_43") (pintype "passive"))
    )
    (net (code "119") (name "unconnected-(STM1-PE13-Pad44)") (class "Default")
      (node (ref "STM1") (pin "44") (pinfunction "PE13_44") (pintype "passive"))
    )
    (net (code "120") (name "unconnected-(STM1-PE14-Pad45)") (class "Default")
      (node (ref "STM1") (pin "45") (pinfunction "PE14_45") (pintype "passive"))
    )
    (net (code "121") (name "unconnected-(STM1-PE15-Pad46)") (class "Default")
      (node (ref "STM1") (pin "46") (pinfunction "PE15_46") (pintype "passive"))
    )
    (net (code "122") (name "unconnected-(STM1-VREF--Pad20)") (class "Default")
      (node (ref "STM1") (pin "20") (pinfunction "VREF-_20") (pintype "passive"))
    )
    (net (code "123") (name "unconnected-(STM1-VSSA-Pad19)") (class "Default")
      (node (ref "STM1") (pin "19") (pinfunction "VSSA_19") (pintype "passive"))
    )
    (net (code "124") (name "unconnected-(STM1-VSS_1-Pad49)") (class "Default")
      (node (ref "STM1") (pin "49") (pinfunction "VSS_1_49") (pintype "passive"))
    )
    (net (code "125") (name "unconnected-(STM1-VSS_2-Pad74)") (class "Default")
      (node (ref "STM1") (pin "74") (pinfunction "VSS_2_74") (pintype "passive"))
    )
    (net (code "126") (name "unconnected-(STM1-VSS_3-Pad99)") (class "Default")
      (node (ref "STM1") (pin "99") (pinfunction "VSS_3_99") (pintype "passive"))
    )
    (net (code "127") (name "unconnected-(STM1-VSS_4-Pad27)") (class "Default")
      (node (ref "STM1") (pin "27") (pinfunction "VSS_4_27") (pintype "passive"))
    )
    (net (code "128") (name "unconnected-(STM1-VSS_5-Pad10)") (class "Default")
      (node (ref "STM1") (pin "10") (pinfunction "VSS_5_10") (pintype "passive"))
    )
  )
)
